# hm-cc-vd.net
KiCad netlist of a schematic drawn in EAGLE
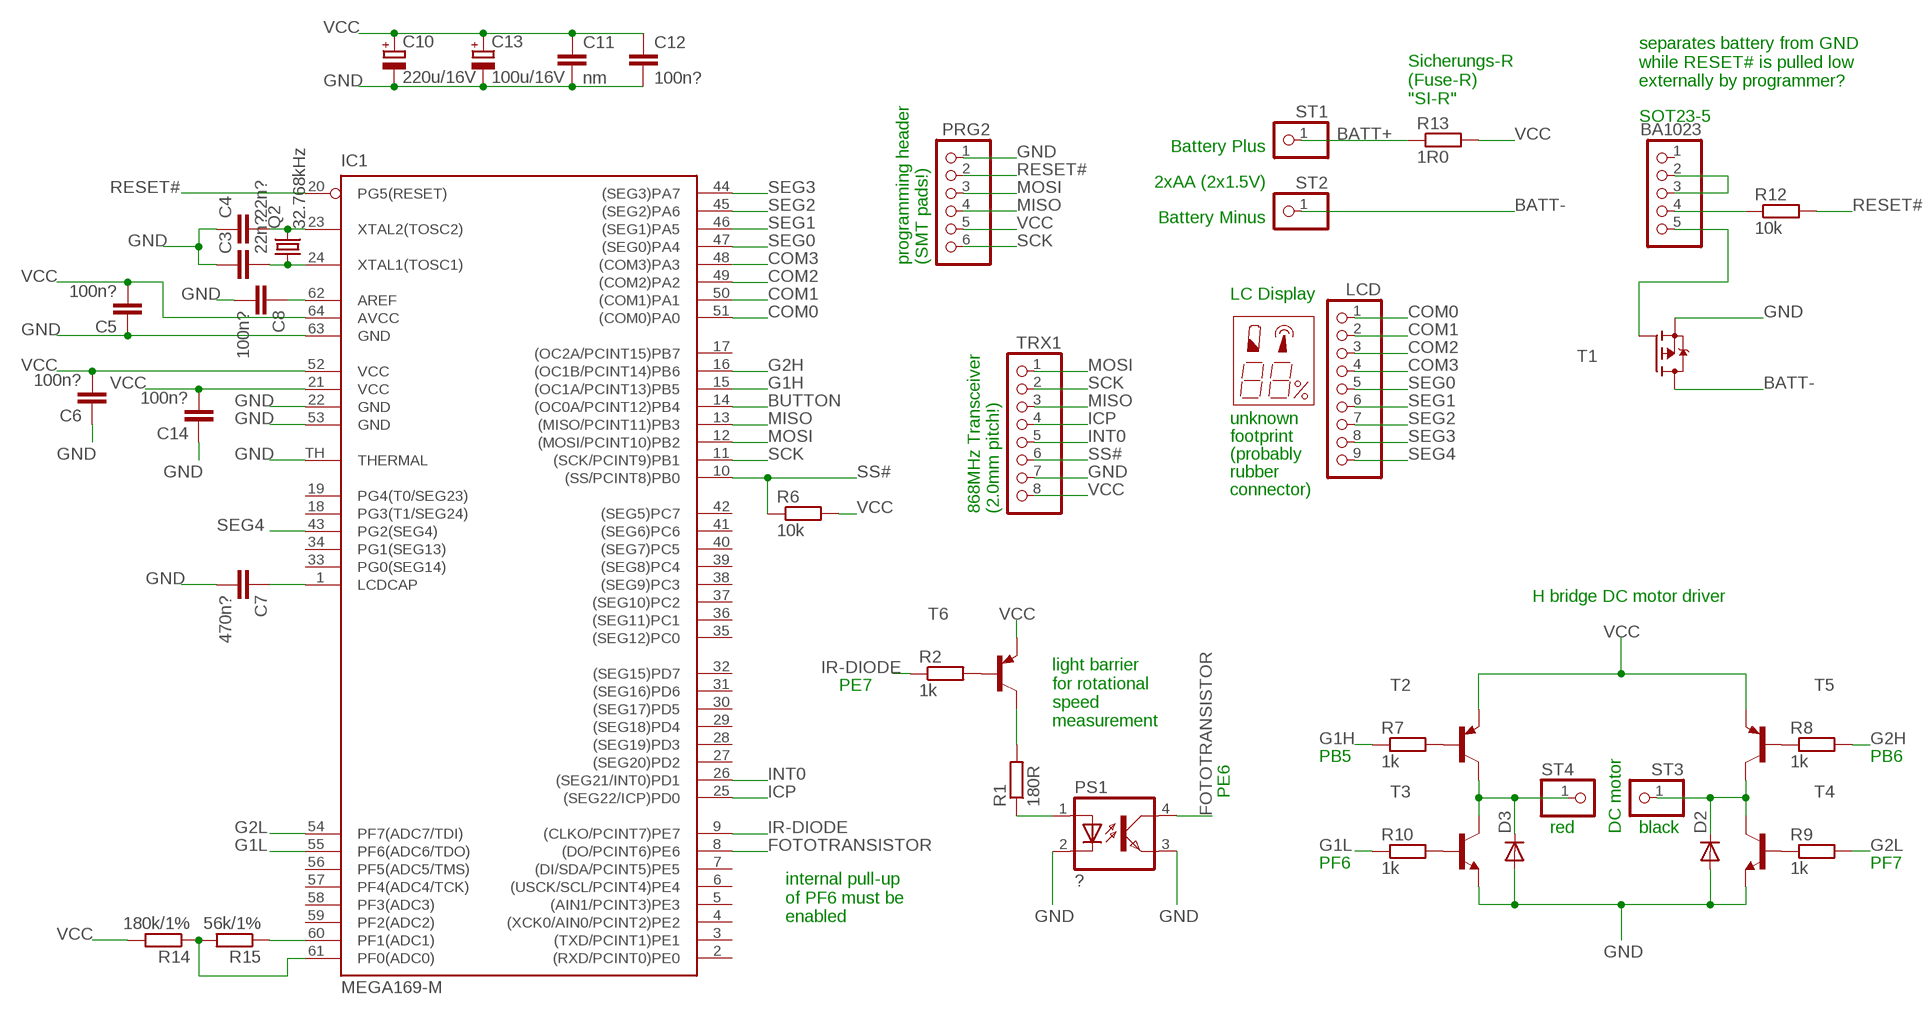
[diagram p0: schematic, sheet 1]

(export (version "E")
  (design (tool "Eeschema 10.0.6"))
  (components
    (comp (ref "BA1023")
      (value "PINHD-1X5")
      (footprint "eagle-import:1X05")
      (libsource (lib "eagle-import") (part "PINHD-1X5"))
    )
    (comp (ref "C3")
      (value "22n?")
      (footprint "eagle-import:C0603K")
      (libsource (lib "eagle-import") (part "C-EUC0603K"))
    )
    (comp (ref "C4")
      (value "22n?")
      (footprint "eagle-import:C0603K")
      (libsource (lib "eagle-import") (part "C-EUC0603K"))
    )
    (comp (ref "C5")
      (value "100n?")
      (footprint "eagle-import:C0805")
      (libsource (lib "eagle-import") (part "C-EUC0805"))
    )
    (comp (ref "C6")
      (value "100n?")
      (footprint "eagle-import:C0805")
      (libsource (lib "eagle-import") (part "C-EUC0805"))
    )
    (comp (ref "C7")
      (value "470n?")
      (footprint "eagle-import:C0805")
      (libsource (lib "eagle-import") (part "C-EUC0805"))
    )
    (comp (ref "C8")
      (value "100n?")
      (footprint "eagle-import:C0805")
      (libsource (lib "eagle-import") (part "C-EUC0805"))
    )
    (comp (ref "C10")
      (value "220u/16V")
      (footprint "eagle-import:E3,5-10")
      (libsource (lib "eagle-import") (part "CPOL-EUE3.5-10"))
    )
    (comp (ref "C11")
      (value "nm")
      (footprint "eagle-import:C0805")
      (libsource (lib "eagle-import") (part "C-EUC0805"))
    )
    (comp (ref "C12")
      (value "100n?")
      (footprint "eagle-import:C0805")
      (libsource (lib "eagle-import") (part "C-EUC0805"))
    )
    (comp (ref "C13")
      (value "100u/16V")
      (footprint "eagle-import:E2,5-6E")
      (libsource (lib "eagle-import") (part "CPOL-EUE2,5-6E"))
    )
    (comp (ref "C14")
      (value "100n?")
      (footprint "eagle-import:C0805")
      (libsource (lib "eagle-import") (part "C-EUC0805"))
    )
    (comp (ref "D2")
      (value "DIODE-MELF-MLL41")
      (footprint "eagle-import:MELF-MLL41")
      (libsource (lib "eagle-import") (part "DIODE-MELF-MLL41"))
    )
    (comp (ref "D3")
      (value "DIODE-MELF-MLL41")
      (footprint "eagle-import:MELF-MLL41")
      (libsource (lib "eagle-import") (part "DIODE-MELF-MLL41"))
    )
    (comp (ref "IC1")
      (value "MEGA169-M")
      (footprint "eagle-import:MLF64-TH")
      (libsource (lib "eagle-import") (part "MEGA169-M"))
    )
    (comp (ref "LCD")
      (value "PINHD-1X9")
      (footprint "eagle-import:1X09")
      (libsource (lib "eagle-import") (part "PINHD-1X9"))
    )
    (comp (ref "PRG2")
      (value "PINHD-1X6")
      (footprint "eagle-import:1X06")
      (libsource (lib "eagle-import") (part "PINHD-1X6"))
    )
    (comp (ref "PS1")
      (value "?")
      (footprint "eagle-import:DIL04")
      (libsource (lib "eagle-import") (part "LTV816"))
    )
    (comp (ref "Q2")
      (value "32.768kHz")
      (footprint "eagle-import:TC26H")
      (libsource (lib "eagle-import") (part "CRYSTALTC26H"))
    )
    (comp (ref "R1")
      (value "180R")
      (footprint "eagle-import:R0805")
      (libsource (lib "eagle-import") (part "R-EU_R0805"))
    )
    (comp (ref "R2")
      (value "1k")
      (footprint "eagle-import:R0805")
      (libsource (lib "eagle-import") (part "R-EU_R0805"))
    )
    (comp (ref "R6")
      (value "10k")
      (footprint "eagle-import:R0805")
      (libsource (lib "eagle-import") (part "R-EU_R0805"))
    )
    (comp (ref "R7")
      (value "1k")
      (footprint "eagle-import:R0805")
      (libsource (lib "eagle-import") (part "R-EU_R0805"))
    )
    (comp (ref "R8")
      (value "1k")
      (footprint "eagle-import:R0805")
      (libsource (lib "eagle-import") (part "R-EU_R0805"))
    )
    (comp (ref "R9")
      (value "1k")
      (footprint "eagle-import:R0805")
      (libsource (lib "eagle-import") (part "R-EU_R0805"))
    )
    (comp (ref "R10")
      (value "1k")
      (footprint "eagle-import:R0805")
      (libsource (lib "eagle-import") (part "R-EU_R0805"))
    )
    (comp (ref "R12")
      (value "10k")
      (footprint "eagle-import:R0805")
      (libsource (lib "eagle-import") (part "R-EU_R0805"))
    )
    (comp (ref "R13")
      (value "1R0")
      (footprint "eagle-import:R0805")
      (libsource (lib "eagle-import") (part "R-EU_R0805"))
    )
    (comp (ref "R14")
      (value "180k/1%")
      (footprint "eagle-import:R0805")
      (libsource (lib "eagle-import") (part "R-EU_R0805"))
    )
    (comp (ref "R15")
      (value "56k/1%")
      (footprint "eagle-import:R0805")
      (libsource (lib "eagle-import") (part "R-EU_R0805"))
    )
    (comp (ref "ST1")
      (value "PINHD-1X1")
      (footprint "eagle-import:1X01")
      (libsource (lib "eagle-import") (part "PINHD-1X1"))
    )
    (comp (ref "ST2")
      (value "PINHD-1X1")
      (footprint "eagle-import:1X01")
      (libsource (lib "eagle-import") (part "PINHD-1X1"))
    )
    (comp (ref "ST3")
      (value "PINHD-1X1")
      (footprint "eagle-import:1X01")
      (libsource (lib "eagle-import") (part "PINHD-1X1"))
    )
    (comp (ref "ST4")
      (value "PINHD-1X1")
      (footprint "eagle-import:1X01")
      (libsource (lib "eagle-import") (part "PINHD-1X1"))
    )
    (comp (ref "T1")
      (value "BSA223SP")
      (footprint "eagle-import:SC75_INFINEON")
      (libsource (lib "eagle-import") (part "BSA223SP"))
    )
    (comp (ref "T2")
      (value "-PNP-SOT23-BCE")
      (footprint "eagle-import:SOT23-BCE")
      (libsource (lib "eagle-import") (part "-PNP-SOT23-BCE"))
    )
    (comp (ref "T3")
      (value "-NPN-SOT23-EBC")
      (footprint "eagle-import:SOT23-EBC")
      (libsource (lib "eagle-import") (part "-NPN-SOT23-EBC"))
    )
    (comp (ref "T4")
      (value "-NPN-SOT23-EBC")
      (footprint "eagle-import:SOT23-EBC")
      (libsource (lib "eagle-import") (part "-NPN-SOT23-EBC"))
    )
    (comp (ref "T5")
      (value "-PNP-SOT23-BCE")
      (footprint "eagle-import:SOT23-BCE")
      (libsource (lib "eagle-import") (part "-PNP-SOT23-BCE"))
    )
    (comp (ref "T6")
      (value "-PNP-SOT23-BCE")
      (footprint "eagle-import:SOT23-BCE")
      (libsource (lib "eagle-import") (part "-PNP-SOT23-BCE"))
    )
    (comp (ref "TRX1")
      (value "PINHD-1X8")
      (footprint "eagle-import:1X08")
      (libsource (lib "eagle-import") (part "PINHD-1X8"))
    )
  )
  (nets
    (net (code "1") (name "/BATT+") (class "Default")
      (node (ref "R13") (pin "1") (pinfunction "1_1") (pintype "passive"))
      (node (ref "ST1") (pin "1") (pinfunction "1_1") (pintype "passive"))
    )
    (net (code "2") (name "/BATT-") (class "Default")
      (node (ref "ST2") (pin "1") (pinfunction "1_1") (pintype "passive"))
      (node (ref "T1") (pin "2") (pinfunction "D_2") (pintype "passive"))
    )
    (net (code "3") (name "/BUTTON") (class "Default")
      (node (ref "IC1") (pin "14") (pinfunction "(OC0A/PCINT12)PB4_14") (pintype "bidirectional"))
    )
    (net (code "4") (name "/COM0") (class "Default")
      (node (ref "IC1") (pin "51") (pinfunction "(COM0)PA0_51") (pintype "bidirectional"))
      (node (ref "LCD") (pin "1") (pinfunction "1_1") (pintype "passive"))
    )
    (net (code "5") (name "/COM1") (class "Default")
      (node (ref "IC1") (pin "50") (pinfunction "(COM1)PA1_50") (pintype "bidirectional"))
      (node (ref "LCD") (pin "2") (pinfunction "2_2") (pintype "passive"))
    )
    (net (code "6") (name "/COM2") (class "Default")
      (node (ref "IC1") (pin "49") (pinfunction "(COM2)PA2_49") (pintype "bidirectional"))
      (node (ref "LCD") (pin "3") (pinfunction "3_3") (pintype "passive"))
    )
    (net (code "7") (name "/COM3") (class "Default")
      (node (ref "IC1") (pin "48") (pinfunction "(COM3)PA3_48") (pintype "bidirectional"))
      (node (ref "LCD") (pin "4") (pinfunction "4_4") (pintype "passive"))
    )
    (net (code "8") (name "/FOTOTRANSISTOR") (class "Default")
      (node (ref "IC1") (pin "8") (pinfunction "(DO/PCINT6)PE6_8") (pintype "bidirectional"))
      (node (ref "PS1") (pin "4") (pinfunction "COL_4") (pintype "passive"))
    )
    (net (code "9") (name "/G1H") (class "Default")
      (node (ref "IC1") (pin "15") (pinfunction "(OC1A/PCINT13)PB5_15") (pintype "bidirectional"))
      (node (ref "R7") (pin "1") (pinfunction "1_1") (pintype "passive"))
    )
    (net (code "10") (name "/G1L") (class "Default")
      (node (ref "IC1") (pin "55") (pinfunction "PF6(ADC6/TDO)_55") (pintype "input"))
      (node (ref "R10") (pin "1") (pinfunction "1_1") (pintype "passive"))
    )
    (net (code "11") (name "/G2H") (class "Default")
      (node (ref "IC1") (pin "16") (pinfunction "(OC1B/PCINT14)PB6_16") (pintype "bidirectional"))
      (node (ref "R8") (pin "2") (pinfunction "2_2") (pintype "passive"))
    )
    (net (code "12") (name "/G2L") (class "Default")
      (node (ref "IC1") (pin "54") (pinfunction "PF7(ADC7/TDI)_54") (pintype "input"))
      (node (ref "R9") (pin "2") (pinfunction "2_2") (pintype "passive"))
    )
    (net (code "13") (name "/GND") (class "Default")
      (node (ref "C10") (pin "-") (pinfunction "-_-") (pintype "passive"))
      (node (ref "C11") (pin "2") (pinfunction "2_2") (pintype "passive"))
      (node (ref "C12") (pin "2") (pinfunction "2_2") (pintype "passive"))
      (node (ref "C13") (pin "-") (pinfunction "-_-") (pintype "passive"))
      (node (ref "C14") (pin "1") (pinfunction "1_1") (pintype "passive"))
      (node (ref "C3") (pin "1") (pinfunction "1_1") (pintype "passive"))
      (node (ref "C4") (pin "1") (pinfunction "1_1") (pintype "passive"))
      (node (ref "C5") (pin "1") (pinfunction "1_1") (pintype "passive"))
      (node (ref "C6") (pin "1") (pinfunction "1_1") (pintype "passive"))
      (node (ref "C7") (pin "2") (pinfunction "2_2") (pintype "passive"))
      (node (ref "C8") (pin "2") (pinfunction "2_2") (pintype "passive"))
      (node (ref "D2") (pin "A") (pinfunction "A_A") (pintype "passive"))
      (node (ref "D3") (pin "A") (pinfunction "A_A") (pintype "passive"))
      (node (ref "IC1") (pin "22") (pinfunction "GND_22") (pintype "power_in"))
      (node (ref "IC1") (pin "53") (pinfunction "GND_53") (pintype "power_in"))
      (node (ref "IC1") (pin "63") (pinfunction "GND_63") (pintype "power_in"))
      (node (ref "IC1") (pin "TH") (pinfunction "THERMAL_TH") (pintype "input"))
      (node (ref "PRG2") (pin "1") (pinfunction "1_1") (pintype "passive"))
      (node (ref "PS1") (pin "2") (pinfunction "C_2") (pintype "passive"))
      (node (ref "PS1") (pin "3") (pinfunction "EMIT_3") (pintype "passive"))
      (node (ref "T1") (pin "3") (pinfunction "S_3") (pintype "passive"))
      (node (ref "T3") (pin "E") (pinfunction "E_E") (pintype "passive"))
      (node (ref "T4") (pin "E") (pinfunction "E_E") (pintype "passive"))
      (node (ref "TRX1") (pin "7") (pinfunction "7_7") (pintype "passive"))
    )
    (net (code "14") (name "/ICP") (class "Default")
      (node (ref "IC1") (pin "25") (pinfunction "(SEG22/ICP)PD0_25") (pintype "bidirectional"))
      (node (ref "TRX1") (pin "4") (pinfunction "4_4") (pintype "passive"))
    )
    (net (code "15") (name "/INT0") (class "Default")
      (node (ref "IC1") (pin "26") (pinfunction "(SEG21/INT0)PD1_26") (pintype "bidirectional"))
      (node (ref "TRX1") (pin "5") (pinfunction "5_5") (pintype "passive"))
    )
    (net (code "16") (name "/IR-DIODE") (class "Default")
      (node (ref "IC1") (pin "9") (pinfunction "(CLKO/PCINT7)PE7_9") (pintype "bidirectional"))
      (node (ref "R2") (pin "1") (pinfunction "1_1") (pintype "passive"))
    )
    (net (code "17") (name "/MISO") (class "Default")
      (node (ref "IC1") (pin "13") (pinfunction "(MISO/PCINT11)PB3_13") (pintype "bidirectional"))
      (node (ref "PRG2") (pin "4") (pinfunction "4_4") (pintype "passive"))
      (node (ref "TRX1") (pin "3") (pinfunction "3_3") (pintype "passive"))
    )
    (net (code "18") (name "/MOSI") (class "Default")
      (node (ref "IC1") (pin "12") (pinfunction "(MOSI/PCINT10)PB2_12") (pintype "bidirectional"))
      (node (ref "PRG2") (pin "3") (pinfunction "3_3") (pintype "passive"))
      (node (ref "TRX1") (pin "1") (pinfunction "1_1") (pintype "passive"))
    )
    (net (code "19") (name "/RESET#") (class "Default")
      (node (ref "IC1") (pin "20") (pinfunction "PG5(RESET)_20") (pintype "input"))
      (node (ref "PRG2") (pin "2") (pinfunction "2_2") (pintype "passive"))
      (node (ref "R12") (pin "2") (pinfunction "2_2") (pintype "passive"))
    )
    (net (code "20") (name "/SCK") (class "Default")
      (node (ref "IC1") (pin "11") (pinfunction "(SCK/PCINT9)PB1_11") (pintype "bidirectional"))
      (node (ref "PRG2") (pin "6") (pinfunction "6_6") (pintype "passive"))
      (node (ref "TRX1") (pin "2") (pinfunction "2_2") (pintype "passive"))
    )
    (net (code "21") (name "/SEG0") (class "Default")
      (node (ref "IC1") (pin "47") (pinfunction "(SEG0)PA4_47") (pintype "bidirectional"))
      (node (ref "LCD") (pin "5") (pinfunction "5_5") (pintype "passive"))
    )
    (net (code "22") (name "/SEG1") (class "Default")
      (node (ref "IC1") (pin "46") (pinfunction "(SEG1)PA5_46") (pintype "bidirectional"))
      (node (ref "LCD") (pin "6") (pinfunction "6_6") (pintype "passive"))
    )
    (net (code "23") (name "/SEG2") (class "Default")
      (node (ref "IC1") (pin "45") (pinfunction "(SEG2)PA6_45") (pintype "bidirectional"))
      (node (ref "LCD") (pin "7") (pinfunction "7_7") (pintype "passive"))
    )
    (net (code "24") (name "/SEG3") (class "Default")
      (node (ref "IC1") (pin "44") (pinfunction "(SEG3)PA7_44") (pintype "bidirectional"))
      (node (ref "LCD") (pin "8") (pinfunction "8_8") (pintype "passive"))
    )
    (net (code "25") (name "/SEG4") (class "Default")
      (node (ref "IC1") (pin "43") (pinfunction "PG2(SEG4)_43") (pintype "bidirectional"))
      (node (ref "LCD") (pin "9") (pinfunction "9_9") (pintype "passive"))
    )
    (net (code "26") (name "/SS#") (class "Default")
      (node (ref "IC1") (pin "10") (pinfunction "(SS/PCINT8)PB0_10") (pintype "bidirectional"))
      (node (ref "R6") (pin "1") (pinfunction "1_1") (pintype "passive"))
      (node (ref "TRX1") (pin "6") (pinfunction "6_6") (pintype "passive"))
    )
    (net (code "27") (name "/VCC") (class "Default")
      (node (ref "C10") (pin "+") (pinfunction "+_+") (pintype "passive"))
      (node (ref "C11") (pin "1") (pinfunction "1_1") (pintype "passive"))
      (node (ref "C12") (pin "1") (pinfunction "1_1") (pintype "passive"))
      (node (ref "C13") (pin "+") (pinfunction "+_+") (pintype "passive"))
      (node (ref "C14") (pin "2") (pinfunction "2_2") (pintype "passive"))
      (node (ref "C5") (pin "2") (pinfunction "2_2") (pintype "passive"))
      (node (ref "C6") (pin "2") (pinfunction "2_2") (pintype "passive"))
      (node (ref "IC1") (pin "21") (pinfunction "VCC_21") (pintype "power_in"))
      (node (ref "IC1") (pin "52") (pinfunction "VCC_52") (pintype "power_in"))
      (node (ref "IC1") (pin "64") (pinfunction "AVCC_64") (pintype "power_in"))
      (node (ref "PRG2") (pin "5") (pinfunction "5_5") (pintype "passive"))
      (node (ref "R13") (pin "2") (pinfunction "2_2") (pintype "passive"))
      (node (ref "R14") (pin "2") (pinfunction "2_2") (pintype "passive"))
      (node (ref "R6") (pin "2") (pinfunction "2_2") (pintype "passive"))
      (node (ref "T2") (pin "E") (pinfunction "E_E") (pintype "passive"))
      (node (ref "T5") (pin "E") (pinfunction "E_E") (pintype "passive"))
      (node (ref "T6") (pin "E") (pinfunction "E_E") (pintype "passive"))
      (node (ref "TRX1") (pin "8") (pinfunction "8_8") (pintype "passive"))
    )
    (net (code "28") (name "Net-(BA1023-Pad2)") (class "Default")
      (node (ref "BA1023") (pin "2") (pinfunction "2_2") (pintype "passive"))
      (node (ref "BA1023") (pin "3") (pinfunction "3_3") (pintype "passive"))
    )
    (net (code "29") (name "Net-(BA1023-Pad4)") (class "Default")
      (node (ref "BA1023") (pin "4") (pinfunction "4_4") (pintype "passive"))
      (node (ref "R12") (pin "1") (pinfunction "1_1") (pintype "passive"))
    )
    (net (code "30") (name "Net-(D2-PadC)") (class "Default")
      (node (ref "D2") (pin "C") (pinfunction "C_C") (pintype "passive"))
      (node (ref "ST3") (pin "1") (pinfunction "1_1") (pintype "passive"))
      (node (ref "T4") (pin "C") (pinfunction "C_C") (pintype "passive"))
      (node (ref "T5") (pin "C") (pinfunction "C_C") (pintype "passive"))
    )
    (net (code "31") (name "Net-(D3-PadC)") (class "Default")
      (node (ref "D3") (pin "C") (pinfunction "C_C") (pintype "passive"))
      (node (ref "ST4") (pin "1") (pinfunction "1_1") (pintype "passive"))
      (node (ref "T2") (pin "C") (pinfunction "C_C") (pintype "passive"))
      (node (ref "T3") (pin "C") (pinfunction "C_C") (pintype "passive"))
    )
    (net (code "32") (name "Net-(IC1-AREF)") (class "Default")
      (node (ref "C8") (pin "1") (pinfunction "1_1") (pintype "passive"))
      (node (ref "IC1") (pin "62") (pinfunction "AREF_62") (pintype "passive"))
    )
    (net (code "33") (name "Net-(IC1-LCDCAP)") (class "Default")
      (node (ref "C7") (pin "1") (pinfunction "1_1") (pintype "passive"))
      (node (ref "IC1") (pin "1") (pinfunction "LCDCAP_1") (pintype "input"))
    )
    (net (code "34") (name "Net-(IC1-PF0(ADC0))") (class "Default")
      (node (ref "IC1") (pin "61") (pinfunction "PF0(ADC0)_61") (pintype "input"))
      (node (ref "R14") (pin "1") (pinfunction "1_1") (pintype "passive"))
      (node (ref "R15") (pin "2") (pinfunction "2_2") (pintype "passive"))
    )
    (net (code "35") (name "Net-(IC1-PF1(ADC1))") (class "Default")
      (node (ref "IC1") (pin "60") (pinfunction "PF1(ADC1)_60") (pintype "input"))
      (node (ref "R15") (pin "1") (pinfunction "1_1") (pintype "passive"))
    )
    (net (code "36") (name "Net-(IC1-XTAL1(TOSC1))") (class "Default")
      (node (ref "C3") (pin "2") (pinfunction "2_2") (pintype "passive"))
      (node (ref "IC1") (pin "24") (pinfunction "XTAL1(TOSC1)_24") (pintype "bidirectional"))
      (node (ref "Q2") (pin "1") (pinfunction "1_1") (pintype "passive"))
    )
    (net (code "37") (name "Net-(IC1-XTAL2(TOSC2))") (class "Default")
      (node (ref "C4") (pin "2") (pinfunction "2_2") (pintype "passive"))
      (node (ref "IC1") (pin "23") (pinfunction "XTAL2(TOSC2)_23") (pintype "bidirectional"))
      (node (ref "Q2") (pin "2") (pinfunction "2_2") (pintype "passive"))
    )
    (net (code "38") (name "Net-(PS1-A)") (class "Default")
      (node (ref "PS1") (pin "1") (pinfunction "A_1") (pintype "passive"))
      (node (ref "R1") (pin "1") (pinfunction "1_1") (pintype "passive"))
    )
    (net (code "39") (name "Net-(R1-Pad2)") (class "Default")
      (node (ref "R1") (pin "2") (pinfunction "2_2") (pintype "passive"))
      (node (ref "T6") (pin "C") (pinfunction "C_C") (pintype "passive"))
    )
    (net (code "40") (name "Net-(R2-Pad2)") (class "Default")
      (node (ref "R2") (pin "2") (pinfunction "2_2") (pintype "passive"))
      (node (ref "T6") (pin "B") (pinfunction "B_B") (pintype "passive"))
    )
    (net (code "41") (name "Net-(R7-Pad2)") (class "Default")
      (node (ref "R7") (pin "2") (pinfunction "2_2") (pintype "passive"))
      (node (ref "T2") (pin "B") (pinfunction "B_B") (pintype "passive"))
    )
    (net (code "42") (name "Net-(R8-Pad1)") (class "Default")
      (node (ref "R8") (pin "1") (pinfunction "1_1") (pintype "passive"))
      (node (ref "T5") (pin "B") (pinfunction "B_B") (pintype "passive"))
    )
    (net (code "43") (name "Net-(R9-Pad1)") (class "Default")
      (node (ref "R9") (pin "1") (pinfunction "1_1") (pintype "passive"))
      (node (ref "T4") (pin "B") (pinfunction "B_B") (pintype "passive"))
    )
    (net (code "44") (name "Net-(R10-Pad2)") (class "Default")
      (node (ref "R10") (pin "2") (pinfunction "2_2") (pintype "passive"))
      (node (ref "T3") (pin "B") (pinfunction "B_B") (pintype "passive"))
    )
    (net (code "45") (name "Net-(T1-G)") (class "Default")
      (node (ref "BA1023") (pin "5") (pinfunction "5_5") (pintype "passive"))
      (node (ref "T1") (pin "1") (pinfunction "G_1") (pintype "passive"))
    )
    (net (code "46") (name "unconnected-(BA1023-Pad1)") (class "Default")
      (node (ref "BA1023") (pin "1") (pinfunction "1_1") (pintype "passive"))
    )
    (net (code "47") (name "unconnected-(IC1-(AIN1{slash}PCINT3)PE3-Pad5)") (class "Default")
      (node (ref "IC1") (pin "5") (pinfunction "(AIN1/PCINT3)PE3_5") (pintype "bidirectional"))
    )
    (net (code "48") (name "unconnected-(IC1-(DI{slash}SDA{slash}PCINT5)PE5-Pad7)") (class "Default")
      (node (ref "IC1") (pin "7") (pinfunction "(DI/SDA/PCINT5)PE5_7") (pintype "bidirectional"))
    )
    (net (code "49") (name "unconnected-(IC1-(OC2A{slash}PCINT15)PB7-Pad17)") (class "Default")
      (node (ref "IC1") (pin "17") (pinfunction "(OC2A/PCINT15)PB7_17") (pintype "bidirectional"))
    )
    (net (code "50") (name "unconnected-(IC1-(RXD{slash}PCINT0)PE0-Pad2)") (class "Default")
      (node (ref "IC1") (pin "2") (pinfunction "(RXD/PCINT0)PE0_2") (pintype "bidirectional"))
    )
    (net (code "51") (name "unconnected-(IC1-(SEG5)PC7-Pad42)") (class "Default")
      (node (ref "IC1") (pin "42") (pinfunction "(SEG5)PC7_42") (pintype "output"))
    )
    (net (code "52") (name "unconnected-(IC1-(SEG6)PC6-Pad41)") (class "Default")
      (node (ref "IC1") (pin "41") (pinfunction "(SEG6)PC6_41") (pintype "output"))
    )
    (net (code "53") (name "unconnected-(IC1-(SEG7)PC5-Pad40)") (class "Default")
      (node (ref "IC1") (pin "40") (pinfunction "(SEG7)PC5_40") (pintype "output"))
    )
    (net (code "54") (name "unconnected-(IC1-(SEG8)PC4-Pad39)") (class "Default")
      (node (ref "IC1") (pin "39") (pinfunction "(SEG8)PC4_39") (pintype "output"))
    )
    (net (code "55") (name "unconnected-(IC1-(SEG9)PC3-Pad38)") (class "Default")
      (node (ref "IC1") (pin "38") (pinfunction "(SEG9)PC3_38") (pintype "output"))
    )
    (net (code "56") (name "unconnected-(IC1-(SEG10)PC2-Pad37)") (class "Default")
      (node (ref "IC1") (pin "37") (pinfunction "(SEG10)PC2_37") (pintype "output"))
    )
    (net (code "57") (name "unconnected-(IC1-(SEG11)PC1-Pad36)") (class "Default")
      (node (ref "IC1") (pin "36") (pinfunction "(SEG11)PC1_36") (pintype "output"))
    )
    (net (code "58") (name "unconnected-(IC1-(SEG12)PC0-Pad35)") (class "Default")
      (node (ref "IC1") (pin "35") (pinfunction "(SEG12)PC0_35") (pintype "output"))
    )
    (net (code "59") (name "unconnected-(IC1-(SEG15)PD7-Pad32)") (class "Default")
      (node (ref "IC1") (pin "32") (pinfunction "(SEG15)PD7_32") (pintype "bidirectional"))
    )
    (net (code "60") (name "unconnected-(IC1-(SEG16)PD6-Pad31)") (class "Default")
      (node (ref "IC1") (pin "31") (pinfunction "(SEG16)PD6_31") (pintype "bidirectional"))
    )
    (net (code "61") (name "unconnected-(IC1-(SEG17)PD5-Pad30)") (class "Default")
      (node (ref "IC1") (pin "30") (pinfunction "(SEG17)PD5_30") (pintype "bidirectional"))
    )
    (net (code "62") (name "unconnected-(IC1-(SEG18)PD4-Pad29)") (class "Default")
      (node (ref "IC1") (pin "29") (pinfunction "(SEG18)PD4_29") (pintype "bidirectional"))
    )
    (net (code "63") (name "unconnected-(IC1-(SEG19)PD3-Pad28)") (class "Default")
      (node (ref "IC1") (pin "28") (pinfunction "(SEG19)PD3_28") (pintype "bidirectional"))
    )
    (net (code "64") (name "unconnected-(IC1-(SEG20)PD2-Pad27)") (class "Default")
      (node (ref "IC1") (pin "27") (pinfunction "(SEG20)PD2_27") (pintype "bidirectional"))
    )
    (net (code "65") (name "unconnected-(IC1-(TXD{slash}PCINT1)PE1-Pad3)") (class "Default")
      (node (ref "IC1") (pin "3") (pinfunction "(TXD/PCINT1)PE1_3") (pintype "bidirectional"))
    )
    (net (code "66") (name "unconnected-(IC1-(USCK{slash}SCL{slash}PCINT4)PE4-Pad6)") (class "Default")
      (node (ref "IC1") (pin "6") (pinfunction "(USCK/SCL/PCINT4)PE4_6") (pintype "bidirectional"))
    )
    (net (code "67") (name "unconnected-(IC1-(XCK0{slash}AIN0{slash}PCINT2)PE2-Pad4)") (class "Default")
      (node (ref "IC1") (pin "4") (pinfunction "(XCK0/AIN0/PCINT2)PE2_4") (pintype "bidirectional"))
    )
    (net (code "68") (name "unconnected-(IC1-PF2(ADC2)-Pad59)") (class "Default")
      (node (ref "IC1") (pin "59") (pinfunction "PF2(ADC2)_59") (pintype "input"))
    )
    (net (code "69") (name "unconnected-(IC1-PF3(ADC3)-Pad58)") (class "Default")
      (node (ref "IC1") (pin "58") (pinfunction "PF3(ADC3)_58") (pintype "input"))
    )
    (net (code "70") (name "unconnected-(IC1-PF4(ADC4{slash}TCK)-Pad57)") (class "Default")
      (node (ref "IC1") (pin "57") (pinfunction "PF4(ADC4/TCK)_57") (pintype "input"))
    )
    (net (code "71") (name "unconnected-(IC1-PF5(ADC5{slash}TMS)-Pad56)") (class "Default")
      (node (ref "IC1") (pin "56") (pinfunction "PF5(ADC5/TMS)_56") (pintype "input"))
    )
    (net (code "72") (name "unconnected-(IC1-PG0(SEG14)-Pad33)") (class "Default")
      (node (ref "IC1") (pin "33") (pinfunction "PG0(SEG14)_33") (pintype "bidirectional"))
    )
    (net (code "73") (name "unconnected-(IC1-PG1(SEG13)-Pad34)") (class "Default")
      (node (ref "IC1") (pin "34") (pinfunction "PG1(SEG13)_34") (pintype "bidirectional"))
    )
    (net (code "74") (name "unconnected-(IC1-PG3(T1{slash}SEG24)-Pad18)") (class "Default")
      (node (ref "IC1") (pin "18") (pinfunction "PG3(T1/SEG24)_18") (pintype "bidirectional"))
    )
    (net (code "75") (name "unconnected-(IC1-PG4(T0{slash}SEG23)-Pad19)") (class "Default")
      (node (ref "IC1") (pin "19") (pinfunction "PG4(T0/SEG23)_19") (pintype "bidirectional"))
    )
  )
)
